# 1-Schematic_ProjectPCB.net
KiCad netlist of a schematic drawn in EasyEDA
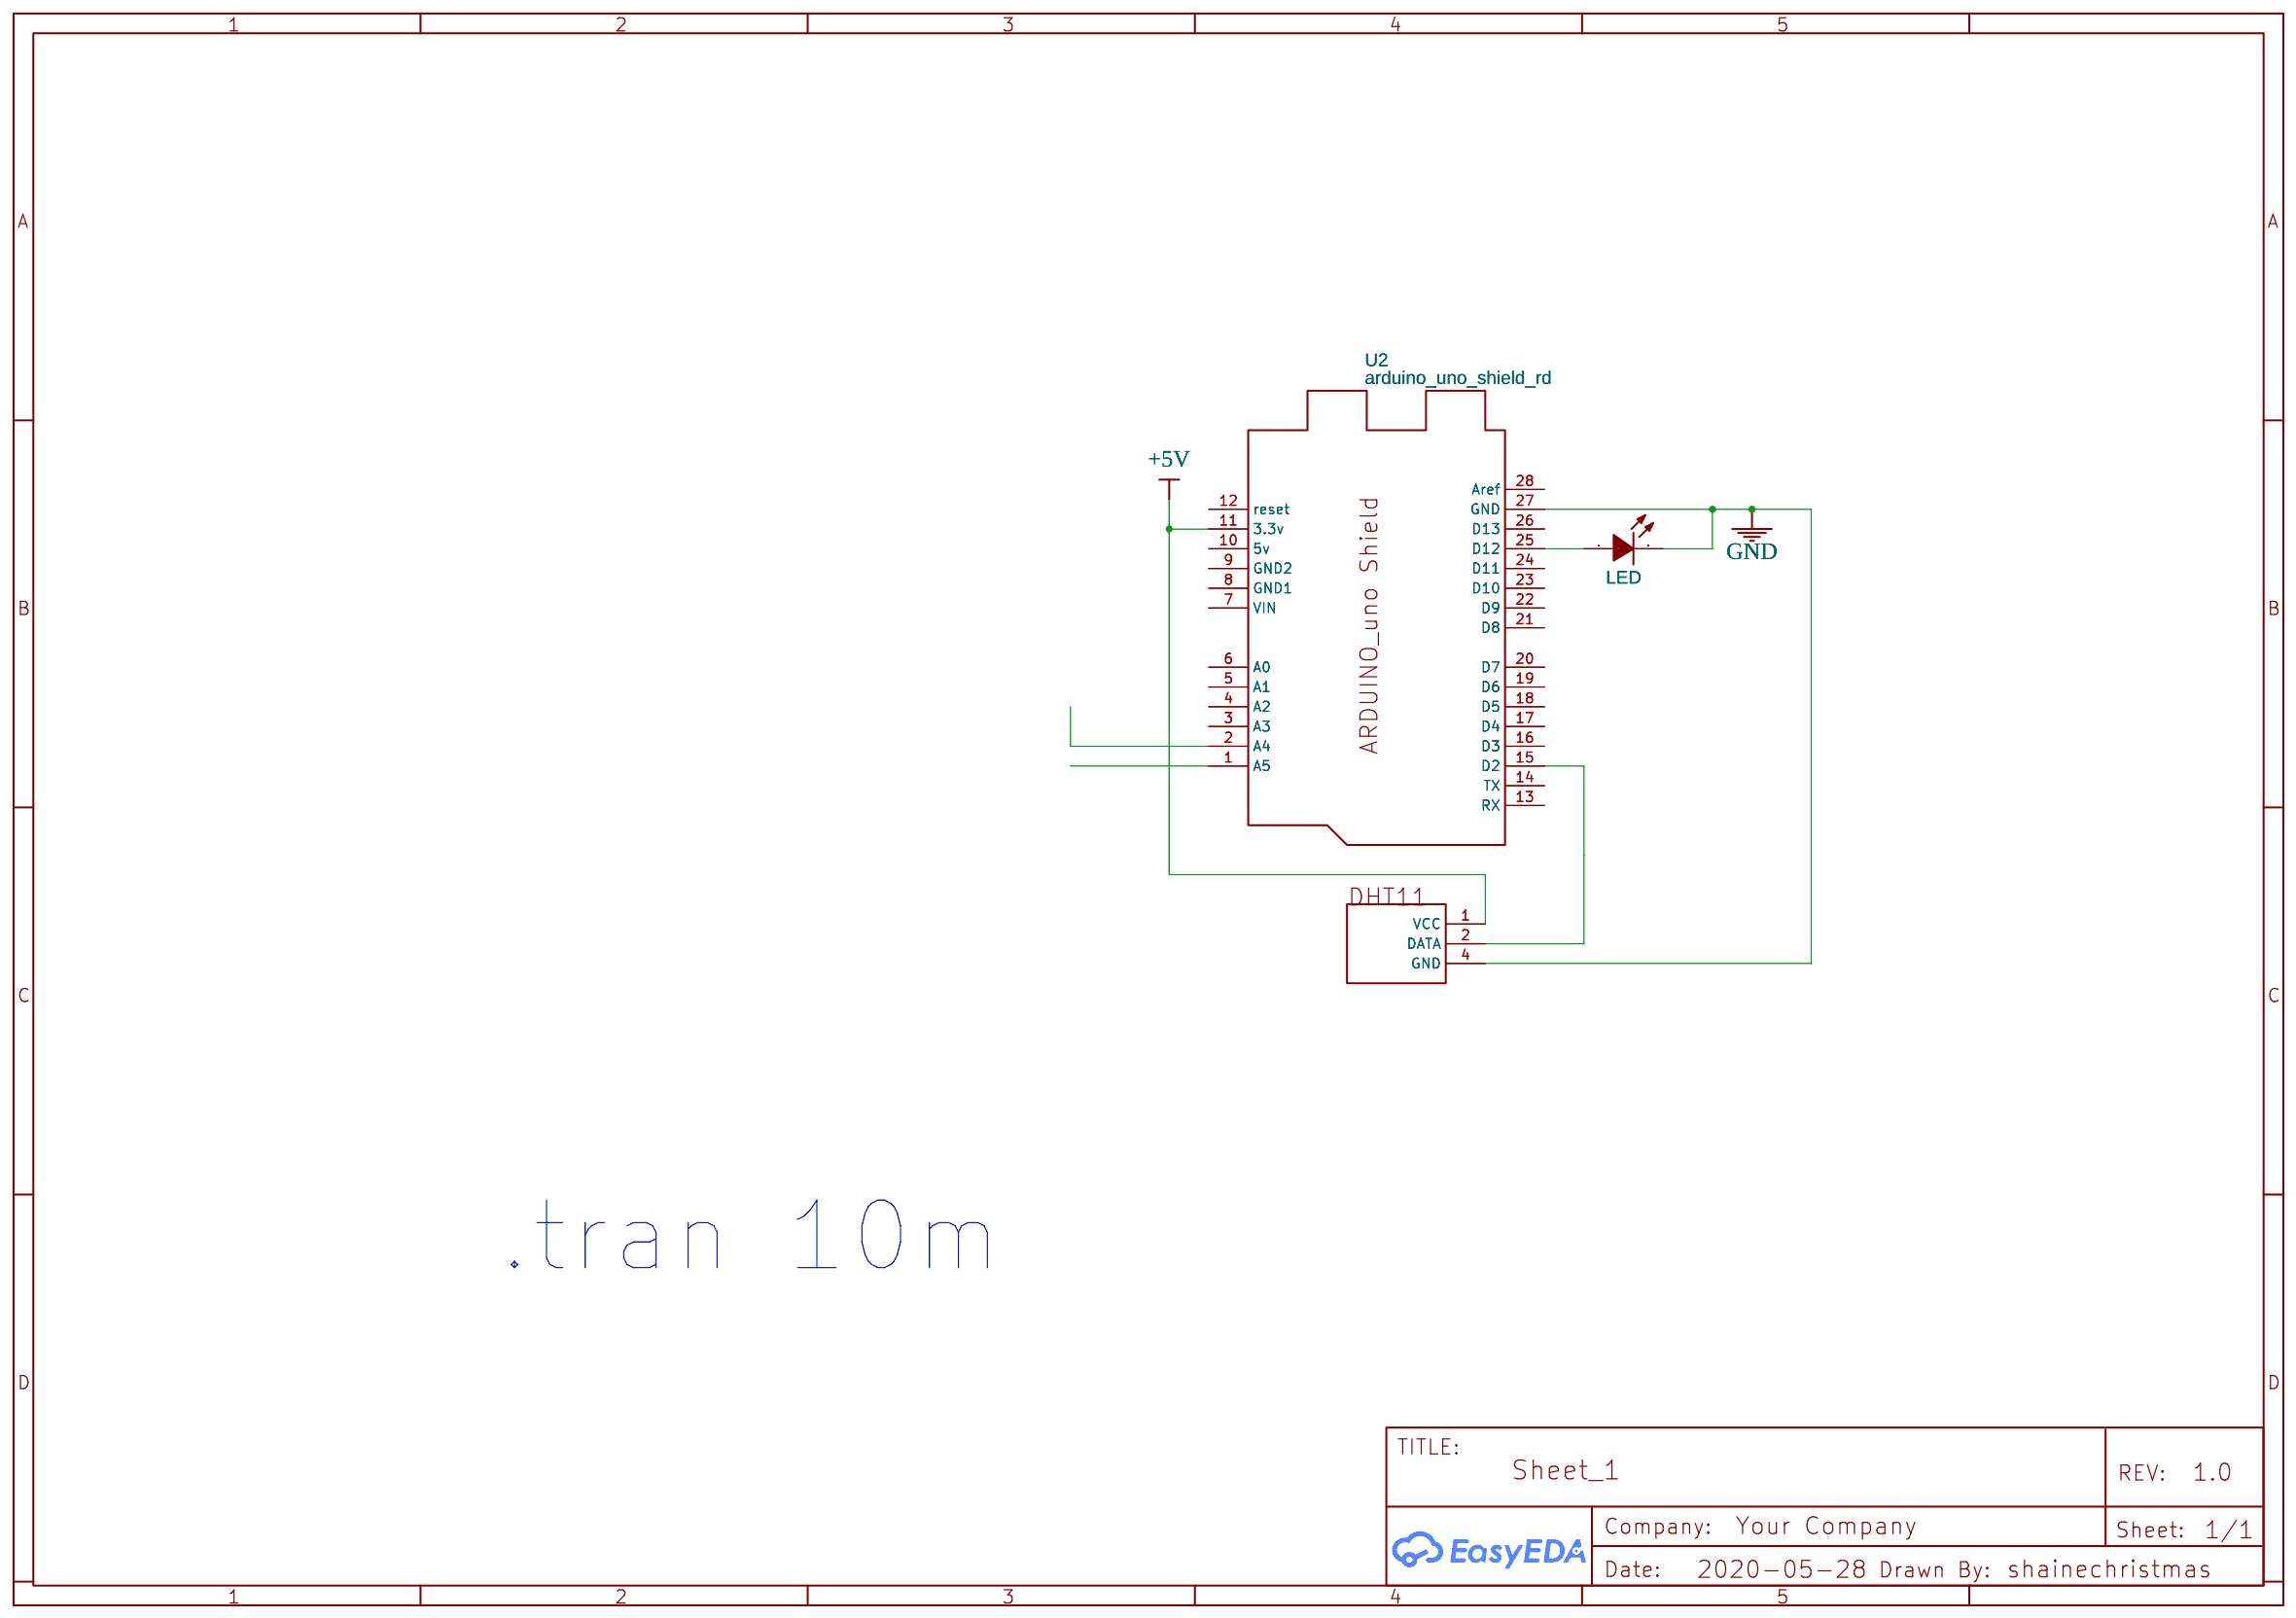
[diagram p0: schematic sheet]

(export (version "E")
  (design (tool "Eeschema 10.0.6"))
  (components
    (comp (ref "D1") (value "LED") (libsource (lib "") (part "LED")))
    (comp (ref "U2") (value "arduino_uno_shield_rd") (libsource (lib "") (part "arduino_uno_shield_rd")))
    (comp (ref "U3") (value "DHT11 COPY") (libsource (lib "") (part "DHT11 COPY")))
  )
  (nets
    (net (code "1") (name "+5V") (class "Default")
      (node (ref "U2") (pin "11") (pinfunction "3.3v_11") (pintype "unspecified"))
      (node (ref "U3") (pin "1") (pinfunction "VCC_1") (pintype "unspecified"))
    )
    (net (code "2") (name "GND") (class "Default")
      (node (ref "D1") (pin "2") (pinfunction "K_2") (pintype "unspecified"))
      (node (ref "U2") (pin "27") (pinfunction "GND_27") (pintype "unspecified"))
      (node (ref "U3") (pin "4") (pinfunction "GND_4") (pintype "unspecified"))
    )
    (net (code "3") (name "Net-(D1-A)") (class "Default")
      (node (ref "D1") (pin "1") (pinfunction "A_1") (pintype "unspecified"))
      (node (ref "U2") (pin "25") (pinfunction "D12_25") (pintype "unspecified"))
    )
    (net (code "4") (name "Net-(U2-D2)") (class "Default")
      (node (ref "U2") (pin "15") (pinfunction "D2_15") (pintype "unspecified"))
      (node (ref "U3") (pin "2") (pinfunction "DATA_2") (pintype "unspecified"))
    )
    (net (code "5") (name "unconnected-(U2-5v-Pad10)") (class "Default")
      (node (ref "U2") (pin "10") (pinfunction "5v_10") (pintype "unspecified"))
    )
    (net (code "6") (name "unconnected-(U2-A0-Pad6)") (class "Default")
      (node (ref "U2") (pin "6") (pinfunction "A0_6") (pintype "unspecified"))
    )
    (net (code "7") (name "unconnected-(U2-A1-Pad5)") (class "Default")
      (node (ref "U2") (pin "5") (pinfunction "A1_5") (pintype "unspecified"))
    )
    (net (code "8") (name "unconnected-(U2-A2-Pad4)") (class "Default")
      (node (ref "U2") (pin "4") (pinfunction "A2_4") (pintype "unspecified"))
    )
    (net (code "9") (name "unconnected-(U2-A3-Pad3)") (class "Default")
      (node (ref "U2") (pin "3") (pinfunction "A3_3") (pintype "unspecified"))
    )
    (net (code "10") (name "unconnected-(U2-A4-Pad2)") (class "Default")
      (node (ref "U2") (pin "2") (pinfunction "A4_2") (pintype "unspecified"))
    )
    (net (code "11") (name "unconnected-(U2-A5-Pad1)") (class "Default")
      (node (ref "U2") (pin "1") (pinfunction "A5_1") (pintype "unspecified"))
    )
    (net (code "12") (name "unconnected-(U2-Aref-Pad28)") (class "Default")
      (node (ref "U2") (pin "28") (pinfunction "Aref_28") (pintype "unspecified"))
    )
    (net (code "13") (name "unconnected-(U2-D3-Pad16)") (class "Default")
      (node (ref "U2") (pin "16") (pinfunction "D3_16") (pintype "unspecified"))
    )
    (net (code "14") (name "unconnected-(U2-D4-Pad17)") (class "Default")
      (node (ref "U2") (pin "17") (pinfunction "D4_17") (pintype "unspecified"))
    )
    (net (code "15") (name "unconnected-(U2-D5-Pad18)") (class "Default")
      (node (ref "U2") (pin "18") (pinfunction "D5_18") (pintype "unspecified"))
    )
    (net (code "16") (name "unconnected-(U2-D6-Pad19)") (class "Default")
      (node (ref "U2") (pin "19") (pinfunction "D6_19") (pintype "unspecified"))
    )
    (net (code "17") (name "unconnected-(U2-D7-Pad20)") (class "Default")
      (node (ref "U2") (pin "20") (pinfunction "D7_20") (pintype "unspecified"))
    )
    (net (code "18") (name "unconnected-(U2-D8-Pad21)") (class "Default")
      (node (ref "U2") (pin "21") (pinfunction "D8_21") (pintype "unspecified"))
    )
    (net (code "19") (name "unconnected-(U2-D9-Pad22)") (class "Default")
      (node (ref "U2") (pin "22") (pinfunction "D9_22") (pintype "unspecified"))
    )
    (net (code "20") (name "unconnected-(U2-D10-Pad23)") (class "Default")
      (node (ref "U2") (pin "23") (pinfunction "D10_23") (pintype "unspecified"))
    )
    (net (code "21") (name "unconnected-(U2-D11-Pad24)") (class "Default")
      (node (ref "U2") (pin "24") (pinfunction "D11_24") (pintype "unspecified"))
    )
    (net (code "22") (name "unconnected-(U2-D13-Pad26)") (class "Default")
      (node (ref "U2") (pin "26") (pinfunction "D13_26") (pintype "unspecified"))
    )
    (net (code "23") (name "unconnected-(U2-GND1-Pad8)") (class "Default")
      (node (ref "U2") (pin "8") (pinfunction "GND1_8") (pintype "unspecified"))
    )
    (net (code "24") (name "unconnected-(U2-GND2-Pad9)") (class "Default")
      (node (ref "U2") (pin "9") (pinfunction "GND2_9") (pintype "unspecified"))
    )
    (net (code "25") (name "unconnected-(U2-RX-Pad13)") (class "Default")
      (node (ref "U2") (pin "13") (pinfunction "RX_13") (pintype "unspecified"))
    )
    (net (code "26") (name "unconnected-(U2-TX-Pad14)") (class "Default")
      (node (ref "U2") (pin "14") (pinfunction "TX_14") (pintype "unspecified"))
    )
    (net (code "27") (name "unconnected-(U2-VIN-Pad7)") (class "Default")
      (node (ref "U2") (pin "7") (pinfunction "VIN_7") (pintype "unspecified"))
    )
    (net (code "28") (name "unconnected-(U2-reset-Pad12)") (class "Default")
      (node (ref "U2") (pin "12") (pinfunction "reset_12") (pintype "unspecified"))
    )
  )
)
